# BUSConnector.net
KiCad netlist of a schematic drawn in Altium Designer
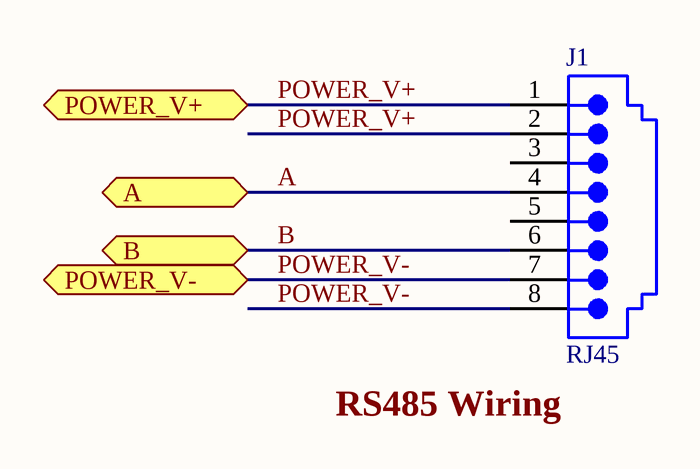
[diagram p0: BUSConnector.SchDoc]

(export (version "E")
  (design (tool "Eeschema 10.0.6"))
  (components
    (comp (ref "J1")
      (value "RJ45")
      (footprint "15-43-6233")
      (description "Conectores modulares / Conectores Ethernet 8 PCB LO PRO R/A")
      (fields (field (name "MPN") "5555164-1"))
      (libsource (lib "Molex Modular Jack Right Angle") (part "15-43-6233"))
    )
  )
  (nets
    (net (code "1") (name "/A") (class "Default")
      (node (ref "J1") (pin "4") (pinfunction "4_4") (pintype "passive"))
    )
    (net (code "2") (name "/B") (class "Default")
      (node (ref "J1") (pin "6") (pinfunction "6_6") (pintype "passive"))
    )
    (net (code "3") (name "/POWER_V+") (class "Default")
      (node (ref "J1") (pin "1") (pinfunction "1_1") (pintype "passive"))
      (node (ref "J1") (pin "2") (pinfunction "2_2") (pintype "passive"))
    )
    (net (code "4") (name "/POWER_V-") (class "Default")
      (node (ref "J1") (pin "7") (pinfunction "7_7") (pintype "passive"))
      (node (ref "J1") (pin "8") (pinfunction "8_8") (pintype "passive"))
    )
    (net (code "6") (name "unconnected-(J1-Pad3)") (class "Default")
      (node (ref "J1") (pin "3") (pinfunction "3_3") (pintype "passive"))
    )
    (net (code "7") (name "unconnected-(J1-Pad5)") (class "Default")
      (node (ref "J1") (pin "5") (pinfunction "5_5") (pintype "passive"))
    )
  )
)
